# sensor.net
KiCad netlist of a schematic drawn in EAGLE
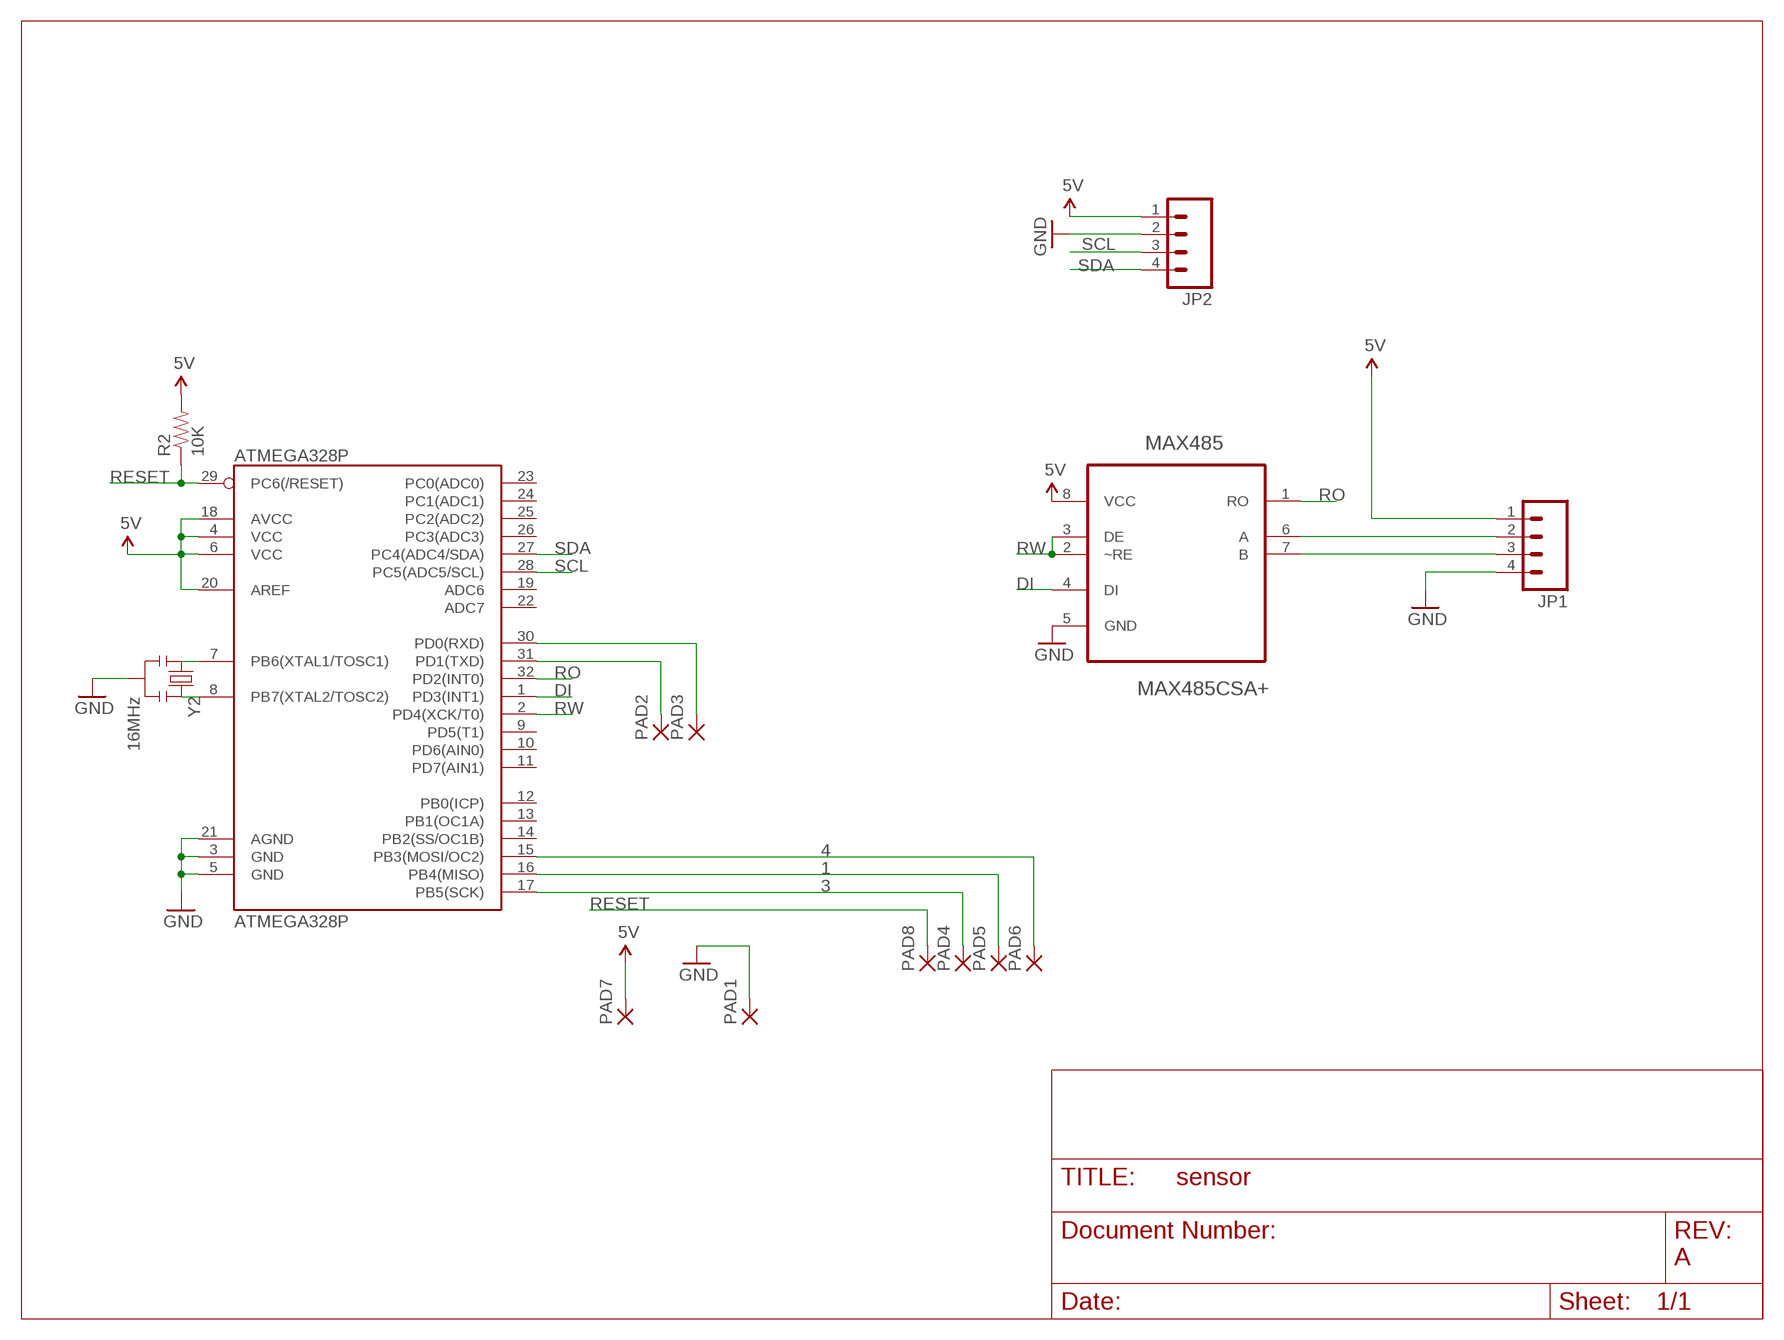
[diagram p0: schematic, sheet 1]

(export (version "E")
  (design (tool "Eeschema 10.0.6"))
  (components
    (comp (ref "ATMEGA328P")
      (value "ATMEGA328P")
      (footprint "eagle-import:TQFP32-08")
      (libsource (lib "eagle-import") (part "ATMEGA328_SMT"))
    )
    (comp (ref "JP1")
      (value "M04PTH")
      (footprint "eagle-import:1X04")
      (libsource (lib "eagle-import") (part "M04PTH"))
    )
    (comp (ref "JP2")
      (value "M04PTH")
      (footprint "eagle-import:1X04")
      (libsource (lib "eagle-import") (part "M04PTH"))
    )
    (comp (ref "MAX485")
      (value "MAX485CSA+")
      (footprint "eagle-import:SOIC127P600X175-8N")
      (libsource (lib "eagle-import") (part "MAX485CSA+"))
    )
    (comp (ref "PAD1")
      (value "1,6/0,9")
      (footprint "eagle-import:1,6_0,9")
      (libsource (lib "eagle-import") (part "1,6/0,9"))
    )
    (comp (ref "PAD2")
      (value "1,6/0,9")
      (footprint "eagle-import:1,6_0,9")
      (libsource (lib "eagle-import") (part "1,6/0,9"))
    )
    (comp (ref "PAD3")
      (value "1,6/0,9")
      (footprint "eagle-import:1,6_0,9")
      (libsource (lib "eagle-import") (part "1,6/0,9"))
    )
    (comp (ref "PAD4")
      (value "1,6/0,9")
      (footprint "eagle-import:1,6_0,9")
      (libsource (lib "eagle-import") (part "1,6/0,9"))
    )
    (comp (ref "PAD5")
      (value "1,6/0,9")
      (footprint "eagle-import:1,6_0,9")
      (libsource (lib "eagle-import") (part "1,6/0,9"))
    )
    (comp (ref "PAD6")
      (value "1,6/0,9")
      (footprint "eagle-import:1,6_0,9")
      (libsource (lib "eagle-import") (part "1,6/0,9"))
    )
    (comp (ref "PAD7")
      (value "1,6/0,9")
      (footprint "eagle-import:1,6_0,9")
      (libsource (lib "eagle-import") (part "1,6/0,9"))
    )
    (comp (ref "PAD8")
      (value "1,6/0,9")
      (footprint "eagle-import:1,6_0,9")
      (libsource (lib "eagle-import") (part "1,6/0,9"))
    )
    (comp (ref "R2")
      (value "10K")
      (footprint "eagle-import:0603-RES")
      (libsource (lib "eagle-import") (part "RESISTOR0603-RES"))
    )
    (comp (ref "Y2")
      (value "16MHz")
      (footprint "eagle-import:RESONATOR-SMD")
      (libsource (lib "eagle-import") (part "RESONATOR16MHZ"))
    )
  )
  (nets
    (net (code "1") (name "/1") (class "Default")
      (node (ref "ATMEGA328P") (pin "16") (pinfunction "PB4(MISO)_16") (pintype "bidirectional"))
      (node (ref "PAD5") (pin "1") (pinfunction "P_1") (pintype "passive"))
    )
    (net (code "2") (name "/3") (class "Default")
      (node (ref "ATMEGA328P") (pin "17") (pinfunction "PB5(SCK)_17") (pintype "bidirectional"))
      (node (ref "PAD4") (pin "1") (pinfunction "P_1") (pintype "passive"))
    )
    (net (code "3") (name "/4") (class "Default")
      (node (ref "ATMEGA328P") (pin "15") (pinfunction "PB3(MOSI/OC2)_15") (pintype "bidirectional"))
      (node (ref "PAD6") (pin "1") (pinfunction "P_1") (pintype "passive"))
    )
    (net (code "4") (name "/DI") (class "Default")
      (node (ref "ATMEGA328P") (pin "1") (pinfunction "PD3(INT1)_1") (pintype "bidirectional"))
      (node (ref "MAX485") (pin "4") (pinfunction "DI_4") (pintype "input"))
    )
    (net (code "5") (name "/RESET") (class "Default")
      (node (ref "ATMEGA328P") (pin "29") (pinfunction "PC6(/RESET)_29") (pintype "bidirectional"))
      (node (ref "PAD8") (pin "1") (pinfunction "P_1") (pintype "passive"))
      (node (ref "R2") (pin "1") (pinfunction "1_1") (pintype "passive"))
    )
    (net (code "6") (name "/RO") (class "Default")
      (node (ref "ATMEGA328P") (pin "32") (pinfunction "PD2(INT0)_32") (pintype "bidirectional"))
      (node (ref "MAX485") (pin "1") (pinfunction "RO_1") (pintype "output"))
    )
    (net (code "7") (name "/RW") (class "Default")
      (node (ref "ATMEGA328P") (pin "2") (pinfunction "PD4(XCK/T0)_2") (pintype "bidirectional"))
      (node (ref "MAX485") (pin "2") (pinfunction "~{RE}_2") (pintype "input"))
      (node (ref "MAX485") (pin "3") (pinfunction "DE_3") (pintype "input"))
    )
    (net (code "8") (name "/SCL") (class "Default")
      (node (ref "ATMEGA328P") (pin "28") (pinfunction "PC5(ADC5/SCL)_28") (pintype "bidirectional"))
      (node (ref "JP2") (pin "3") (pinfunction "3_3") (pintype "passive"))
    )
    (net (code "9") (name "/SDA") (class "Default")
      (node (ref "ATMEGA328P") (pin "27") (pinfunction "PC4(ADC4/SDA)_27") (pintype "bidirectional"))
      (node (ref "JP2") (pin "4") (pinfunction "4_4") (pintype "passive"))
    )
    (net (code "10") (name "5V") (class "Default")
      (node (ref "ATMEGA328P") (pin "18") (pinfunction "AVCC_18") (pintype "bidirectional"))
      (node (ref "ATMEGA328P") (pin "20") (pinfunction "AREF_20") (pintype "bidirectional"))
      (node (ref "ATMEGA328P") (pin "4") (pinfunction "VCC_4") (pintype "bidirectional"))
      (node (ref "ATMEGA328P") (pin "6") (pinfunction "VCC_6") (pintype "bidirectional"))
      (node (ref "JP1") (pin "1") (pinfunction "1_1") (pintype "passive"))
      (node (ref "JP2") (pin "1") (pinfunction "1_1") (pintype "passive"))
      (node (ref "MAX485") (pin "8") (pinfunction "VCC_8") (pintype "power_in"))
      (node (ref "PAD7") (pin "1") (pinfunction "P_1") (pintype "passive"))
      (node (ref "R2") (pin "2") (pinfunction "2_2") (pintype "passive"))
    )
    (net (code "11") (name "GND") (class "Default")
      (node (ref "ATMEGA328P") (pin "21") (pinfunction "AGND_21") (pintype "bidirectional"))
      (node (ref "ATMEGA328P") (pin "3") (pinfunction "GND_3") (pintype "bidirectional"))
      (node (ref "ATMEGA328P") (pin "5") (pinfunction "GND_5") (pintype "bidirectional"))
      (node (ref "JP1") (pin "4") (pinfunction "4_4") (pintype "passive"))
      (node (ref "JP2") (pin "2") (pinfunction "2_2") (pintype "passive"))
      (node (ref "MAX485") (pin "5") (pinfunction "GND_5") (pintype "passive"))
      (node (ref "PAD1") (pin "1") (pinfunction "P_1") (pintype "passive"))
      (node (ref "Y2") (pin "2") (pinfunction "2_2") (pintype "passive"))
    )
    (net (code "12") (name "Net-(ATMEGA328P-PB6(XTAL1{slash}TOSC1))") (class "Default")
      (node (ref "ATMEGA328P") (pin "7") (pinfunction "PB6(XTAL1/TOSC1)_7") (pintype "bidirectional"))
      (node (ref "Y2") (pin "1") (pinfunction "1_1") (pintype "passive"))
    )
    (net (code "13") (name "Net-(ATMEGA328P-PB7(XTAL2{slash}TOSC2))") (class "Default")
      (node (ref "ATMEGA328P") (pin "8") (pinfunction "PB7(XTAL2/TOSC2)_8") (pintype "bidirectional"))
      (node (ref "Y2") (pin "3") (pinfunction "3_3") (pintype "passive"))
    )
    (net (code "14") (name "Net-(ATMEGA328P-PD0(RXD))") (class "Default")
      (node (ref "ATMEGA328P") (pin "30") (pinfunction "PD0(RXD)_30") (pintype "bidirectional"))
      (node (ref "PAD3") (pin "1") (pinfunction "P_1") (pintype "passive"))
    )
    (net (code "15") (name "Net-(ATMEGA328P-PD1(TXD))") (class "Default")
      (node (ref "ATMEGA328P") (pin "31") (pinfunction "PD1(TXD)_31") (pintype "bidirectional"))
      (node (ref "PAD2") (pin "1") (pinfunction "P_1") (pintype "passive"))
    )
    (net (code "16") (name "Net-(MAX485-A)") (class "Default")
      (node (ref "JP1") (pin "2") (pinfunction "2_2") (pintype "passive"))
      (node (ref "MAX485") (pin "6") (pinfunction "A_6") (pintype "bidirectional"))
    )
    (net (code "17") (name "Net-(MAX485-B)") (class "Default")
      (node (ref "JP1") (pin "3") (pinfunction "3_3") (pintype "passive"))
      (node (ref "MAX485") (pin "7") (pinfunction "B_7") (pintype "bidirectional"))
    )
    (net (code "18") (name "unconnected-(ATMEGA328P-ADC6-Pad19)") (class "Default")
      (node (ref "ATMEGA328P") (pin "19") (pinfunction "ADC6_19") (pintype "bidirectional"))
    )
    (net (code "19") (name "unconnected-(ATMEGA328P-ADC7-Pad22)") (class "Default")
      (node (ref "ATMEGA328P") (pin "22") (pinfunction "ADC7_22") (pintype "bidirectional"))
    )
    (net (code "20") (name "unconnected-(ATMEGA328P-PB0(ICP)-Pad12)") (class "Default")
      (node (ref "ATMEGA328P") (pin "12") (pinfunction "PB0(ICP)_12") (pintype "bidirectional"))
    )
    (net (code "21") (name "unconnected-(ATMEGA328P-PB1(OC1A)-Pad13)") (class "Default")
      (node (ref "ATMEGA328P") (pin "13") (pinfunction "PB1(OC1A)_13") (pintype "bidirectional"))
    )
    (net (code "22") (name "unconnected-(ATMEGA328P-PB2(SS{slash}OC1B)-Pad14)") (class "Default")
      (node (ref "ATMEGA328P") (pin "14") (pinfunction "PB2(SS/OC1B)_14") (pintype "bidirectional"))
    )
    (net (code "23") (name "unconnected-(ATMEGA328P-PC0(ADC0)-Pad23)") (class "Default")
      (node (ref "ATMEGA328P") (pin "23") (pinfunction "PC0(ADC0)_23") (pintype "bidirectional"))
    )
    (net (code "24") (name "unconnected-(ATMEGA328P-PC1(ADC1)-Pad24)") (class "Default")
      (node (ref "ATMEGA328P") (pin "24") (pinfunction "PC1(ADC1)_24") (pintype "bidirectional"))
    )
    (net (code "25") (name "unconnected-(ATMEGA328P-PC2(ADC2)-Pad25)") (class "Default")
      (node (ref "ATMEGA328P") (pin "25") (pinfunction "PC2(ADC2)_25") (pintype "bidirectional"))
    )
    (net (code "26") (name "unconnected-(ATMEGA328P-PC3(ADC3)-Pad26)") (class "Default")
      (node (ref "ATMEGA328P") (pin "26") (pinfunction "PC3(ADC3)_26") (pintype "bidirectional"))
    )
    (net (code "27") (name "unconnected-(ATMEGA328P-PD5(T1)-Pad9)") (class "Default")
      (node (ref "ATMEGA328P") (pin "9") (pinfunction "PD5(T1)_9") (pintype "bidirectional"))
    )
    (net (code "28") (name "unconnected-(ATMEGA328P-PD6(AIN0)-Pad10)") (class "Default")
      (node (ref "ATMEGA328P") (pin "10") (pinfunction "PD6(AIN0)_10") (pintype "bidirectional"))
    )
    (net (code "29") (name "unconnected-(ATMEGA328P-PD7(AIN1)-Pad11)") (class "Default")
      (node (ref "ATMEGA328P") (pin "11") (pinfunction "PD7(AIN1)_11") (pintype "bidirectional"))
    )
  )
)
